# NanoLogger.net
KiCad netlist of a schematic drawn in EAGLE
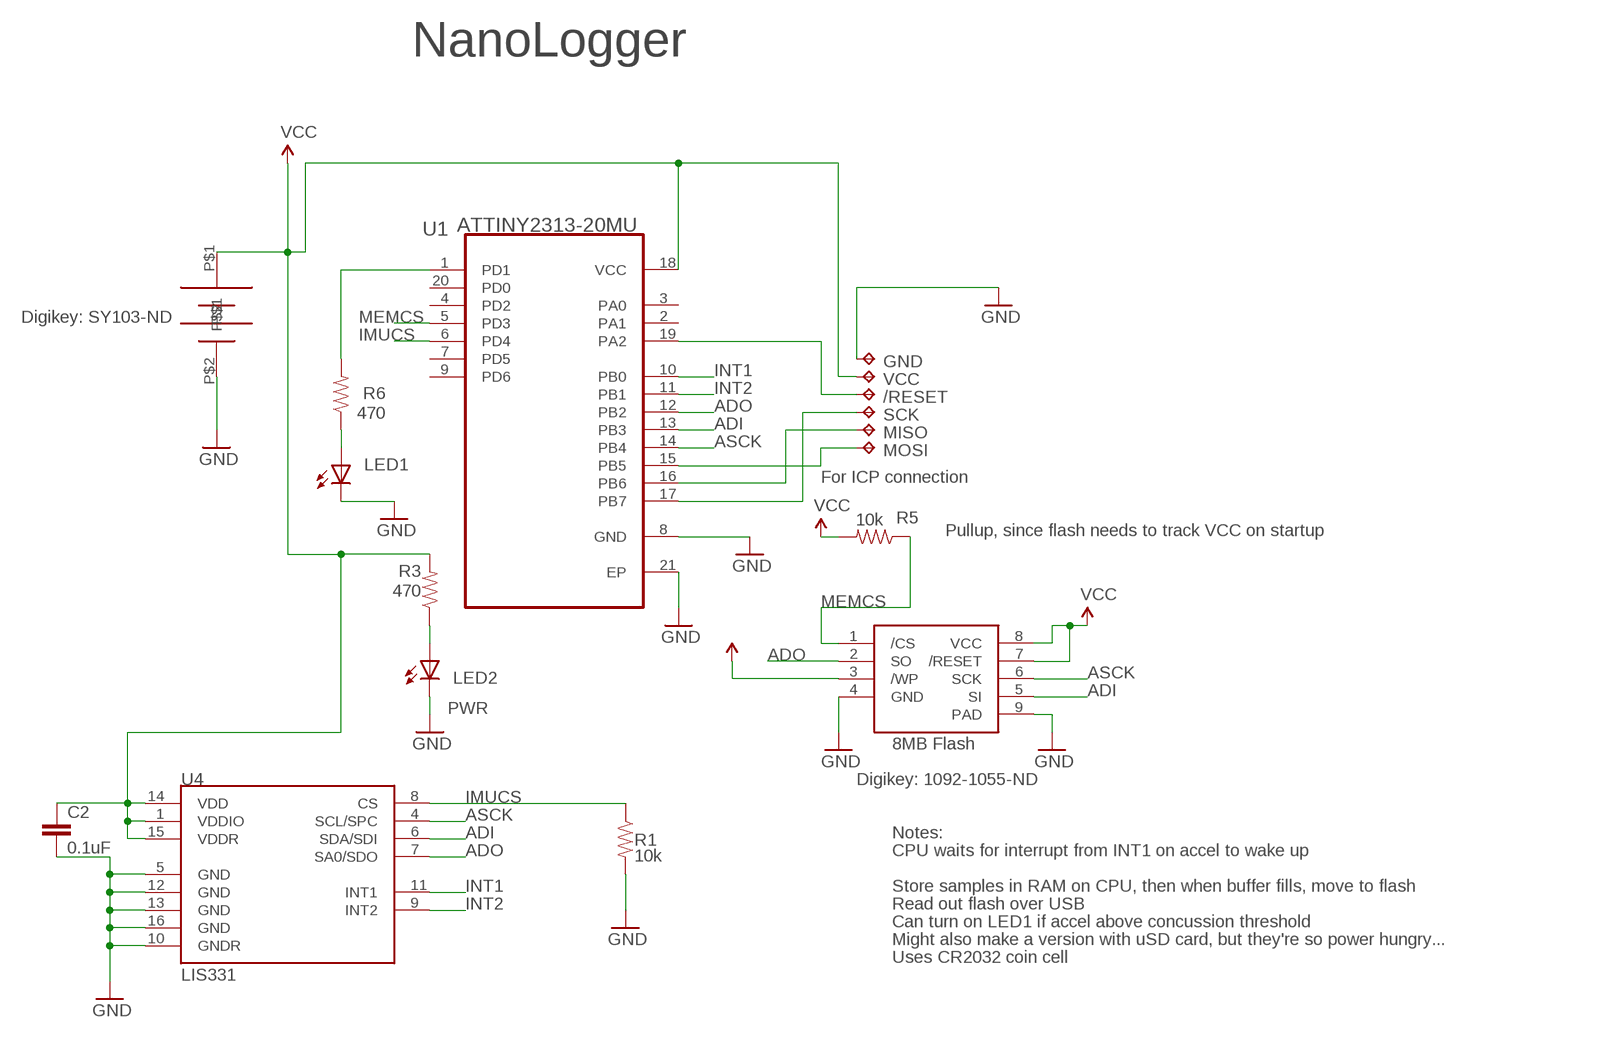
[diagram p0: schematic, sheet 1]

(export (version "E")
  (design (tool "Eeschema 10.0.6"))
  (components
    (comp (ref "/RESET")
      (value "TPTP08R")
      (footprint "eagle-import:TP08R")
      (libsource (lib "eagle-import") (part "TPTP08R"))
    )
    (comp (ref "C2")
      (value "0.1uF")
      (footprint "eagle-import:0402-CAP")
      (libsource (lib "eagle-import") (part "CAP0402-CAP"))
    )
    (comp (ref "GND")
      (value "TPTP08R")
      (footprint "eagle-import:TP08R")
      (libsource (lib "eagle-import") (part "TPTP08R"))
    )
    (comp (ref "LED1")
      (value "LED0603")
      (footprint "eagle-import:LED-0603")
      (libsource (lib "eagle-import") (part "LED0603"))
    )
    (comp (ref "LED2")
      (value "LED0603")
      (footprint "eagle-import:LED-0603")
      (libsource (lib "eagle-import") (part "LED0603"))
    )
    (comp (ref "MISO")
      (value "TPTP08R")
      (footprint "eagle-import:TP08R")
      (libsource (lib "eagle-import") (part "TPTP08R"))
    )
    (comp (ref "MOSI")
      (value "TPTP08R")
      (footprint "eagle-import:TP08R")
      (libsource (lib "eagle-import") (part "TPTP08R"))
    )
    (comp (ref "R1")
      (value "10k")
      (footprint "eagle-import:0402-RES")
      (libsource (lib "eagle-import") (part "RESISTOR0402-RES"))
    )
    (comp (ref "R3")
      (value "470")
      (footprint "eagle-import:0402-RES")
      (libsource (lib "eagle-import") (part "RESISTOR0402-RES"))
    )
    (comp (ref "R5")
      (value "10k")
      (footprint "eagle-import:0402-RES")
      (libsource (lib "eagle-import") (part "RESISTOR0402-RES"))
    )
    (comp (ref "R6")
      (value "470")
      (footprint "eagle-import:0402-RES")
      (libsource (lib "eagle-import") (part "RESISTOR0402-RES"))
    )
    (comp (ref "SCK")
      (value "TPTP08R")
      (footprint "eagle-import:TP08R")
      (libsource (lib "eagle-import") (part "TPTP08R"))
    )
    (comp (ref "U$1")
      (value "ML621-TZ1")
      (footprint "eagle-import:ML621-TZ1")
      (libsource (lib "eagle-import") (part "ML621-TZ1"))
    )
    (comp (ref "U$2")
      (value "MX25U8035EZUI-10G")
      (footprint "eagle-import:MX25U8035EZUI-10G")
      (libsource (lib "eagle-import") (part "MX25U8035EZUI-10G"))
    )
    (comp (ref "U1")
      (value "ATTINY2313-20MU")
      (footprint "eagle-import:QFN50P400X400X80-21N")
      (libsource (lib "eagle-import") (part "ATTINY2313-20MU"))
    )
    (comp (ref "U4")
      (value "LIS331")
      (footprint "eagle-import:LGA16-3MM")
      (libsource (lib "eagle-import") (part "LIS331"))
    )
    (comp (ref "VCC")
      (value "TPTP08R")
      (footprint "eagle-import:TP08R")
      (libsource (lib "eagle-import") (part "TPTP08R"))
    )
  )
  (nets
    (net (code "1") (name "/ADI") (class "Default")
      (node (ref "U$2") (pin "5") (pinfunction "SI_5") (pintype "bidirectional"))
      (node (ref "U1") (pin "13") (pinfunction "PB3_13") (pintype "bidirectional"))
      (node (ref "U4") (pin "6") (pinfunction "SDA/SDI_6") (pintype "bidirectional"))
    )
    (net (code "2") (name "/ADO") (class "Default")
      (node (ref "U$2") (pin "2") (pinfunction "SO_2") (pintype "bidirectional"))
      (node (ref "U1") (pin "12") (pinfunction "PB2_12") (pintype "bidirectional"))
      (node (ref "U4") (pin "7") (pinfunction "SA0/SDO_7") (pintype "bidirectional"))
    )
    (net (code "3") (name "/ASCK") (class "Default")
      (node (ref "U$2") (pin "6") (pinfunction "SCK_6") (pintype "bidirectional"))
      (node (ref "U1") (pin "14") (pinfunction "PB4_14") (pintype "bidirectional"))
      (node (ref "U4") (pin "4") (pinfunction "SCL/SPC_4") (pintype "bidirectional"))
    )
    (net (code "4") (name "/IMUCS") (class "Default")
      (node (ref "R1") (pin "1") (pinfunction "1_1") (pintype "passive"))
      (node (ref "U1") (pin "6") (pinfunction "PD4_6") (pintype "bidirectional"))
      (node (ref "U4") (pin "8") (pinfunction "CS_8") (pintype "bidirectional"))
    )
    (net (code "5") (name "/INT1") (class "Default")
      (node (ref "U1") (pin "10") (pinfunction "PB0_10") (pintype "bidirectional"))
      (node (ref "U4") (pin "11") (pinfunction "INT1_11") (pintype "bidirectional"))
    )
    (net (code "6") (name "/INT2") (class "Default")
      (node (ref "U1") (pin "11") (pinfunction "PB1_11") (pintype "bidirectional"))
      (node (ref "U4") (pin "9") (pinfunction "INT2_9") (pintype "bidirectional"))
    )
    (net (code "7") (name "/MEMCS") (class "Default")
      (node (ref "R5") (pin "1") (pinfunction "1_1") (pintype "passive"))
      (node (ref "U$2") (pin "1") (pinfunction "/CS_1") (pintype "bidirectional"))
      (node (ref "U1") (pin "5") (pinfunction "PD3_5") (pintype "bidirectional"))
    )
    (net (code "8") (name "GND") (class "Default")
      (node (ref "C2") (pin "2") (pinfunction "2_2") (pintype "passive"))
      (node (ref "GND") (pin "TP") (pinfunction "TP_TP") (pintype "input"))
      (node (ref "LED1") (pin "C") (pinfunction "C_C") (pintype "passive"))
      (node (ref "LED2") (pin "C") (pinfunction "C_C") (pintype "passive"))
      (node (ref "R1") (pin "2") (pinfunction "2_2") (pintype "passive"))
      (node (ref "U$1") (pin "P$2") (pinfunction "P$1_P$2") (pintype "bidirectional"))
      (node (ref "U$2") (pin "4") (pinfunction "GND_4") (pintype "bidirectional"))
      (node (ref "U$2") (pin "9") (pinfunction "PAD_9") (pintype "bidirectional"))
      (node (ref "U1") (pin "21") (pinfunction "EP_21") (pintype "passive"))
      (node (ref "U1") (pin "8") (pinfunction "GND_8") (pintype "passive"))
      (node (ref "U4") (pin "10") (pinfunction "GNDR_10") (pintype "bidirectional"))
      (node (ref "U4") (pin "12") (pinfunction "GND_12") (pintype "bidirectional"))
      (node (ref "U4") (pin "13") (pinfunction "GND_13") (pintype "bidirectional"))
      (node (ref "U4") (pin "16") (pinfunction "GND_16") (pintype "bidirectional"))
      (node (ref "U4") (pin "5") (pinfunction "GND_5") (pintype "bidirectional"))
    )
    (net (code "9") (name "Net-(LED1-PadA)") (class "Default")
      (node (ref "LED1") (pin "A") (pinfunction "A_A") (pintype "passive"))
      (node (ref "R6") (pin "1") (pinfunction "1_1") (pintype "passive"))
    )
    (net (code "10") (name "Net-(LED2-PadA)") (class "Default")
      (node (ref "LED2") (pin "A") (pinfunction "A_A") (pintype "passive"))
      (node (ref "R3") (pin "1") (pinfunction "1_1") (pintype "passive"))
    )
    (net (code "11") (name "Net-(U1-PA2)") (class "Default")
      (node (ref "/RESET") (pin "TP") (pinfunction "TP_TP") (pintype "input"))
      (node (ref "U1") (pin "19") (pinfunction "PA2_19") (pintype "bidirectional"))
    )
    (net (code "12") (name "Net-(U1-PB5)") (class "Default")
      (node (ref "MOSI") (pin "TP") (pinfunction "TP_TP") (pintype "input"))
      (node (ref "U1") (pin "15") (pinfunction "PB5_15") (pintype "bidirectional"))
    )
    (net (code "13") (name "Net-(U1-PB6)") (class "Default")
      (node (ref "MISO") (pin "TP") (pinfunction "TP_TP") (pintype "input"))
      (node (ref "U1") (pin "16") (pinfunction "PB6_16") (pintype "bidirectional"))
    )
    (net (code "14") (name "Net-(U1-PB7)") (class "Default")
      (node (ref "SCK") (pin "TP") (pinfunction "TP_TP") (pintype "input"))
      (node (ref "U1") (pin "17") (pinfunction "PB7_17") (pintype "bidirectional"))
    )
    (net (code "15") (name "Net-(U1-PD1)") (class "Default")
      (node (ref "R6") (pin "2") (pinfunction "2_2") (pintype "passive"))
      (node (ref "U1") (pin "1") (pinfunction "PD1_1") (pintype "bidirectional"))
    )
    (net (code "16") (name "VCC") (class "Default")
      (node (ref "C2") (pin "1") (pinfunction "1_1") (pintype "passive"))
      (node (ref "R3") (pin "2") (pinfunction "2_2") (pintype "passive"))
      (node (ref "R5") (pin "2") (pinfunction "2_2") (pintype "passive"))
      (node (ref "U$1") (pin "P$1") (pinfunction "P$2_P$1") (pintype "bidirectional"))
      (node (ref "U$2") (pin "3") (pinfunction "/WP_3") (pintype "bidirectional"))
      (node (ref "U$2") (pin "7") (pinfunction "/RESET_7") (pintype "bidirectional"))
      (node (ref "U$2") (pin "8") (pinfunction "VCC_8") (pintype "bidirectional"))
      (node (ref "U1") (pin "18") (pinfunction "VCC_18") (pintype "power_in"))
      (node (ref "U4") (pin "1") (pinfunction "VDDIO_1") (pintype "bidirectional"))
      (node (ref "U4") (pin "14") (pinfunction "VDD_14") (pintype "bidirectional"))
      (node (ref "U4") (pin "15") (pinfunction "VDDR_15") (pintype "bidirectional"))
      (node (ref "VCC") (pin "TP") (pinfunction "TP_TP") (pintype "input"))
    )
    (net (code "17") (name "unconnected-(U1-PA0-Pad3)") (class "Default")
      (node (ref "U1") (pin "3") (pinfunction "PA0_3") (pintype "bidirectional"))
    )
    (net (code "18") (name "unconnected-(U1-PA1-Pad2)") (class "Default")
      (node (ref "U1") (pin "2") (pinfunction "PA1_2") (pintype "bidirectional"))
    )
    (net (code "19") (name "unconnected-(U1-PD0-Pad20)") (class "Default")
      (node (ref "U1") (pin "20") (pinfunction "PD0_20") (pintype "bidirectional"))
    )
    (net (code "20") (name "unconnected-(U1-PD2-Pad4)") (class "Default")
      (node (ref "U1") (pin "4") (pinfunction "PD2_4") (pintype "bidirectional"))
    )
    (net (code "21") (name "unconnected-(U1-PD5-Pad7)") (class "Default")
      (node (ref "U1") (pin "7") (pinfunction "PD5_7") (pintype "bidirectional"))
    )
    (net (code "22") (name "unconnected-(U1-PD6-Pad9)") (class "Default")
      (node (ref "U1") (pin "9") (pinfunction "PD6_9") (pintype "bidirectional"))
    )
  )
)
